# 5V_Power_Supply.net
KiCad netlist of a schematic drawn in Altium Designer
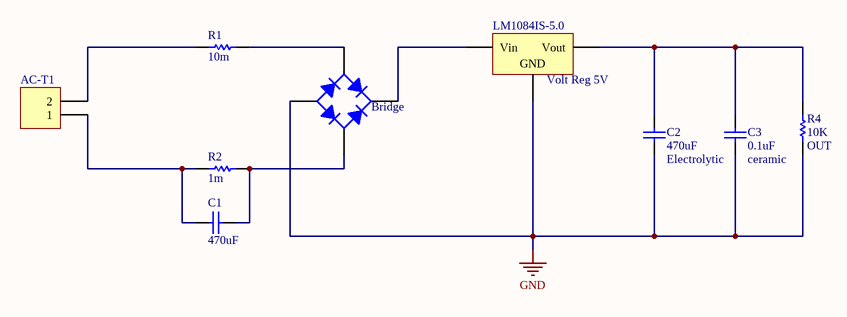
[diagram p0: 5V_Power_Supply.SchDoc]

(export (version "E")
  (design (tool "Eeschema 10.0.6"))
  (components
    (comp (ref "AC-T1")
      (value "~")
      (footprint "MHDR1X2")
      (description "Header, 2-Pin")
      (fields (field (name "PUBLISHER") "Altium Limited"))
      (libsource (lib "Miscellaneous Connectors") (part "MHDR1X2"))
    )
    (comp (ref "Bridge")
      (value "~")
      (footprint "D-38")
      (description "Full Wave Diode Bridge")
      (fields (field (name "PUBLISHER") "Altium Limited"))
      (libsource (lib "Miscellaneous Devices") (part "Bridge1"))
    )
    (comp (ref "C1")
      (value "470uF")
      (footprint "RAD-0.3")
      (description "Capacitor")
      (fields (field (name "PUBLISHER") "Altium Limited"))
      (libsource (lib "Miscellaneous Devices") (part "Cap"))
    )
    (comp (ref "C2")
      (value "Electrolytic")
      (footprint "RAD-0.3")
      (description "Capacitor")
      (fields (field (name "ALTIUM_VALUE") "470uF") (field (name "PUBLISHER") "Altium Limited"))
      (libsource (lib "Miscellaneous Devices") (part "Cap"))
    )
    (comp (ref "C3")
      (value "ceramic")
      (footprint "RAD-0.3")
      (description "Capacitor")
      (fields (field (name "ALTIUM_VALUE") "0.1uF") (field (name "PUBLISHER") "Altium Limited"))
      (libsource (lib "Miscellaneous Devices") (part "Cap"))
    )
    (comp (ref "LM1084IS-5.0")
      (value "Volt Reg 5V")
      (footprint "D2PAK_N")
      (description "Voltage Regulator")
      (fields (field (name "PUBLISHER") "Altium Limited"))
      (libsource (lib "Miscellaneous Devices") (part "Volt Reg"))
    )
    (comp (ref "R1")
      (value "10m")
      (footprint "AXIAL-0.3")
      (description "Resistor")
      (fields (field (name "PUBLISHER") "Altium Limited"))
      (libsource (lib "Miscellaneous Devices") (part "Res1"))
    )
    (comp (ref "R2")
      (value "1m")
      (footprint "AXIAL-0.3")
      (description "Resistor")
      (fields (field (name "PUBLISHER") "Altium Limited"))
      (libsource (lib "Miscellaneous Devices") (part "Res1"))
    )
    (comp (ref "R4")
      (value "OUT")
      (footprint "AXIAL-0.3")
      (description "Resistor")
      (fields (field (name "ALTIUM_VALUE") "10K") (field (name "PUBLISHER") "Altium Limited"))
      (libsource (lib "Miscellaneous Devices") (part "Res1"))
    )
  )
  (nets
    (net (code "1") (name "GND") (class "Default")
      (node (ref "Bridge") (pin "3") (pinfunction "A_3") (pintype "passive"))
      (node (ref "C2") (pin "1") (pinfunction "1_1") (pintype "passive"))
      (node (ref "C3") (pin "1") (pinfunction "1_1") (pintype "passive"))
      (node (ref "LM1084IS-5.0") (pin "2") (pinfunction "GND_2") (pintype "passive"))
      (node (ref "R4") (pin "1") (pinfunction "1_1") (pintype "passive"))
    )
    (net (code "2") (name "Net-(AC-T1-Pad1)") (class "Default")
      (node (ref "AC-T1") (pin "1") (pinfunction "1_1") (pintype "passive"))
      (node (ref "C1") (pin "2") (pinfunction "2_2") (pintype "passive"))
      (node (ref "R2") (pin "2") (pinfunction "2_2") (pintype "passive"))
    )
    (net (code "3") (name "Net-(AC-T1-Pad2)") (class "Default")
      (node (ref "AC-T1") (pin "2") (pinfunction "2_2") (pintype "passive"))
      (node (ref "R1") (pin "2") (pinfunction "2_2") (pintype "passive"))
    )
    (net (code "4") (name "Net-(Bridge-C-Pad2)") (class "Default")
      (node (ref "Bridge") (pin "2") (pinfunction "C_2") (pintype "passive"))
      (node (ref "C1") (pin "1") (pinfunction "1_1") (pintype "passive"))
      (node (ref "R2") (pin "1") (pinfunction "1_1") (pintype "passive"))
    )
    (net (code "5") (name "Net-(Bridge-C-Pad4)") (class "Default")
      (node (ref "Bridge") (pin "4") (pinfunction "C_4") (pintype "passive"))
      (node (ref "R1") (pin "1") (pinfunction "1_1") (pintype "passive"))
    )
    (net (code "6") (name "Net-(Bridge-K)") (class "Default")
      (node (ref "Bridge") (pin "1") (pinfunction "K_1") (pintype "passive"))
      (node (ref "LM1084IS-5.0") (pin "1") (pinfunction "Vin_1") (pintype "passive"))
    )
    (net (code "7") (name "Net-(LM1084IS-5.0-Vout)") (class "Default")
      (node (ref "C2") (pin "2") (pinfunction "2_2") (pintype "passive"))
      (node (ref "C3") (pin "2") (pinfunction "2_2") (pintype "passive"))
      (node (ref "LM1084IS-5.0") (pin "3") (pinfunction "Vout_3") (pintype "passive"))
      (node (ref "R4") (pin "2") (pinfunction "2_2") (pintype "passive"))
    )
  )
)
